# Upload.net
KiCad netlist of a schematic drawn in Altium Designer
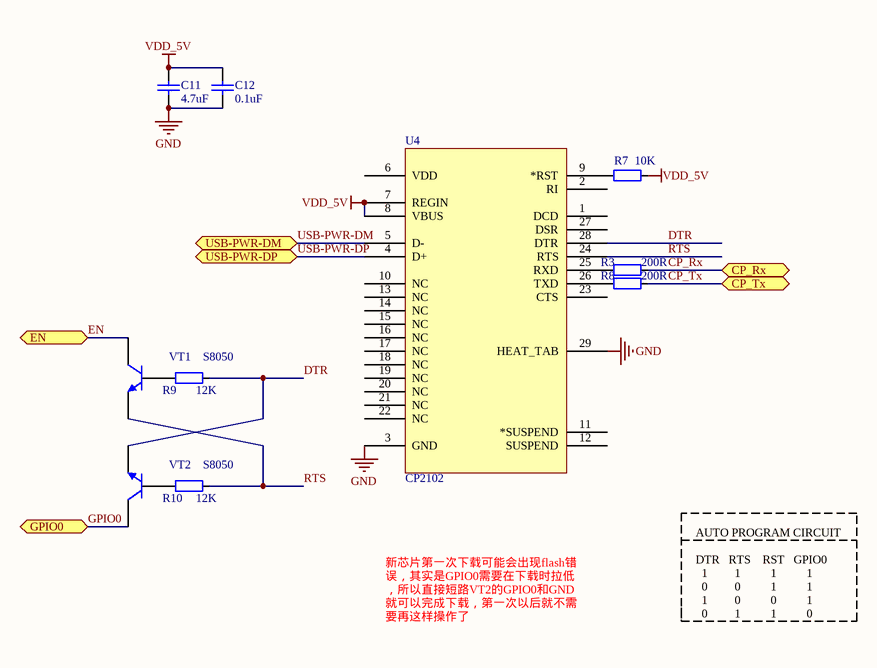
[diagram p0: Upload.SchDoc]

(export (version "E")
  (design (tool "Eeschema 10.0.6"))
  (components
    (comp (ref "C11")
      (value "4.7uF")
      (footprint "C0603")
      (description "Capacitor")
      (fields (field (name "PUBLISHER") "Altium Limited"))
      (libsource (lib "basic") (part "Cap"))
    )
    (comp (ref "C12")
      (value "0.1uF")
      (footprint "C0603")
      (description "Capacitor")
      (fields (field (name "PUBLISHER") "Altium Limited"))
      (libsource (lib "basic") (part "Cap"))
    )
    (comp (ref "R3")
      (value "200R")
      (footprint "R0603")
      (description "Resistor")
      (libsource (lib "MyPcbLib") (part "电阻-0402"))
    )
    (comp (ref "R7")
      (value "10K")
      (footprint "R0603")
      (description "Resistor")
      (libsource (lib "MyPcbLib") (part "电阻-0402"))
    )
    (comp (ref "R8")
      (value "200R")
      (footprint "R0603")
      (description "Resistor")
      (libsource (lib "MyPcbLib") (part "电阻-0402"))
    )
    (comp (ref "R9")
      (value "12K")
      (footprint "R0603")
      (description "Resistor")
      (libsource (lib "MyPcbLib") (part "电阻-0402"))
    )
    (comp (ref "R10")
      (value "12K")
      (footprint "R0603")
      (description "Resistor")
      (libsource (lib "MyPcbLib") (part "电阻-0402"))
    )
    (comp (ref "U4")
      (value "CP2102")
      (footprint "QFN-28")
      (description "USB转TTL")
      (libsource (lib "mLib") (part "CP2102"))
    )
    (comp (ref "VT1")
      (value "S8050")
      (footprint "SMT_TRIODE_NPN")
      (description "Surface mount NPN transistor, package SOT-23")
      (libsource (lib "MyPcbLib") (part "SMT_TRIODE_NPN"))
    )
    (comp (ref "VT2")
      (value "S8050")
      (footprint "SMT_TRIODE_NPN")
      (description "Surface mount NPN transistor, package SOT-23")
      (libsource (lib "MyPcbLib") (part "SMT_TRIODE_NPN"))
    )
  )
  (nets
    (net (code "1") (name "/CP_Rx") (class "Default")
      (node (ref "R3") (pin "1") (pinfunction "1_1") (pintype "passive"))
    )
    (net (code "2") (name "/CP_Tx") (class "Default")
      (node (ref "R8") (pin "1") (pinfunction "1_1") (pintype "passive"))
    )
    (net (code "3") (name "/DTR") (class "Default")
      (node (ref "R9") (pin "1") (pinfunction "1_1") (pintype "passive"))
      (node (ref "U4") (pin "28") (pinfunction "DTR_28") (pintype "passive"))
      (node (ref "VT2") (pin "2") (pinfunction "E_2") (pintype "passive"))
    )
    (net (code "4") (name "/EN") (class "Default")
      (node (ref "VT1") (pin "3") (pinfunction "C_3") (pintype "passive"))
    )
    (net (code "5") (name "/GPIO0") (class "Default")
      (node (ref "VT2") (pin "3") (pinfunction "C_3") (pintype "passive"))
    )
    (net (code "6") (name "/RTS") (class "Default")
      (node (ref "R10") (pin "1") (pinfunction "1_1") (pintype "passive"))
      (node (ref "U4") (pin "24") (pinfunction "RTS_24") (pintype "passive"))
      (node (ref "VT1") (pin "2") (pinfunction "E_2") (pintype "passive"))
    )
    (net (code "7") (name "/USB-PWR-DM") (class "Default")
      (node (ref "U4") (pin "5") (pinfunction "D-_5") (pintype "passive"))
    )
    (net (code "8") (name "/USB-PWR-DP") (class "Default")
      (node (ref "U4") (pin "4") (pinfunction "D+_4") (pintype "passive"))
    )
    (net (code "9") (name "GND") (class "Default")
      (node (ref "C11") (pin "2") (pinfunction "2_2") (pintype "passive"))
      (node (ref "C12") (pin "2") (pinfunction "2_2") (pintype "passive"))
      (node (ref "U4") (pin "29") (pinfunction "HEAT_TAB_29") (pintype "passive"))
      (node (ref "U4") (pin "3") (pinfunction "GND_3") (pintype "passive"))
    )
    (net (code "10") (name "Net-(U4-*RST)") (class "Default")
      (node (ref "R7") (pin "2") (pinfunction "2_2") (pintype "passive"))
      (node (ref "U4") (pin "9") (pinfunction "*RST_9") (pintype "passive"))
    )
    (net (code "11") (name "Net-(U4-RXD)") (class "Default")
      (node (ref "R3") (pin "2") (pinfunction "2_2") (pintype "passive"))
      (node (ref "U4") (pin "25") (pinfunction "RXD_25") (pintype "passive"))
    )
    (net (code "12") (name "Net-(U4-TXD)") (class "Default")
      (node (ref "R8") (pin "2") (pinfunction "2_2") (pintype "passive"))
      (node (ref "U4") (pin "26") (pinfunction "TXD_26") (pintype "passive"))
    )
    (net (code "13") (name "Net-(VT1-B)") (class "Default")
      (node (ref "R9") (pin "2") (pinfunction "2_2") (pintype "passive"))
      (node (ref "VT1") (pin "1") (pinfunction "B_1") (pintype "passive"))
    )
    (net (code "14") (name "Net-(VT2-B)") (class "Default")
      (node (ref "R10") (pin "2") (pinfunction "2_2") (pintype "passive"))
      (node (ref "VT2") (pin "1") (pinfunction "B_1") (pintype "passive"))
    )
    (net (code "15") (name "VDD_5V") (class "Default")
      (node (ref "C11") (pin "1") (pinfunction "1_1") (pintype "passive"))
      (node (ref "C12") (pin "1") (pinfunction "1_1") (pintype "passive"))
      (node (ref "R7") (pin "1") (pinfunction "1_1") (pintype "passive"))
      (node (ref "U4") (pin "7") (pinfunction "REGIN_7") (pintype "passive"))
      (node (ref "U4") (pin "8") (pinfunction "VBUS_8") (pintype "passive"))
    )
    (net (code "16") (name "unconnected-(U4-*SUSPEND-Pad11)") (class "Default")
      (node (ref "U4") (pin "11") (pinfunction "*SUSPEND_11") (pintype "passive"))
    )
    (net (code "17") (name "unconnected-(U4-CTS-Pad23)") (class "Default")
      (node (ref "U4") (pin "23") (pinfunction "CTS_23") (pintype "passive"))
    )
    (net (code "18") (name "unconnected-(U4-DCD-Pad1)") (class "Default")
      (node (ref "U4") (pin "1") (pinfunction "DCD_1") (pintype "passive"))
    )
    (net (code "19") (name "unconnected-(U4-DSR-Pad27)") (class "Default")
      (node (ref "U4") (pin "27") (pinfunction "DSR_27") (pintype "passive"))
    )
    (net (code "20") (name "unconnected-(U4-NC-Pad10)") (class "Default")
      (node (ref "U4") (pin "10") (pinfunction "NC_10") (pintype "passive"))
    )
    (net (code "21") (name "unconnected-(U4-NC-Pad13)") (class "Default")
      (node (ref "U4") (pin "13") (pinfunction "NC_13") (pintype "passive"))
    )
    (net (code "22") (name "unconnected-(U4-NC-Pad14)") (class "Default")
      (node (ref "U4") (pin "14") (pinfunction "NC_14") (pintype "passive"))
    )
    (net (code "23") (name "unconnected-(U4-NC-Pad15)") (class "Default")
      (node (ref "U4") (pin "15") (pinfunction "NC_15") (pintype "passive"))
    )
    (net (code "24") (name "unconnected-(U4-NC-Pad16)") (class "Default")
      (node (ref "U4") (pin "16") (pinfunction "NC_16") (pintype "passive"))
    )
    (net (code "25") (name "unconnected-(U4-NC-Pad17)") (class "Default")
      (node (ref "U4") (pin "17") (pinfunction "NC_17") (pintype "passive"))
    )
    (net (code "26") (name "unconnected-(U4-NC-Pad18)") (class "Default")
      (node (ref "U4") (pin "18") (pinfunction "NC_18") (pintype "passive"))
    )
    (net (code "27") (name "unconnected-(U4-NC-Pad19)") (class "Default")
      (node (ref "U4") (pin "19") (pinfunction "NC_19") (pintype "passive"))
    )
    (net (code "28") (name "unconnected-(U4-NC-Pad20)") (class "Default")
      (node (ref "U4") (pin "20") (pinfunction "NC_20") (pintype "passive"))
    )
    (net (code "29") (name "unconnected-(U4-NC-Pad21)") (class "Default")
      (node (ref "U4") (pin "21") (pinfunction "NC_21") (pintype "passive"))
    )
    (net (code "30") (name "unconnected-(U4-NC-Pad22)") (class "Default")
      (node (ref "U4") (pin "22") (pinfunction "NC_22") (pintype "passive"))
    )
    (net (code "31") (name "unconnected-(U4-RI-Pad2)") (class "Default")
      (node (ref "U4") (pin "2") (pinfunction "RI_2") (pintype "passive"))
    )
    (net (code "32") (name "unconnected-(U4-SUSPEND-Pad12)") (class "Default")
      (node (ref "U4") (pin "12") (pinfunction "SUSPEND_12") (pintype "passive"))
    )
    (net (code "33") (name "unconnected-(U4-VDD-Pad6)") (class "Default")
      (node (ref "U4") (pin "6") (pinfunction "VDD_6") (pintype "passive"))
    )
  )
)
